# CPU.net
KiCad netlist of a schematic drawn in Altium Designer
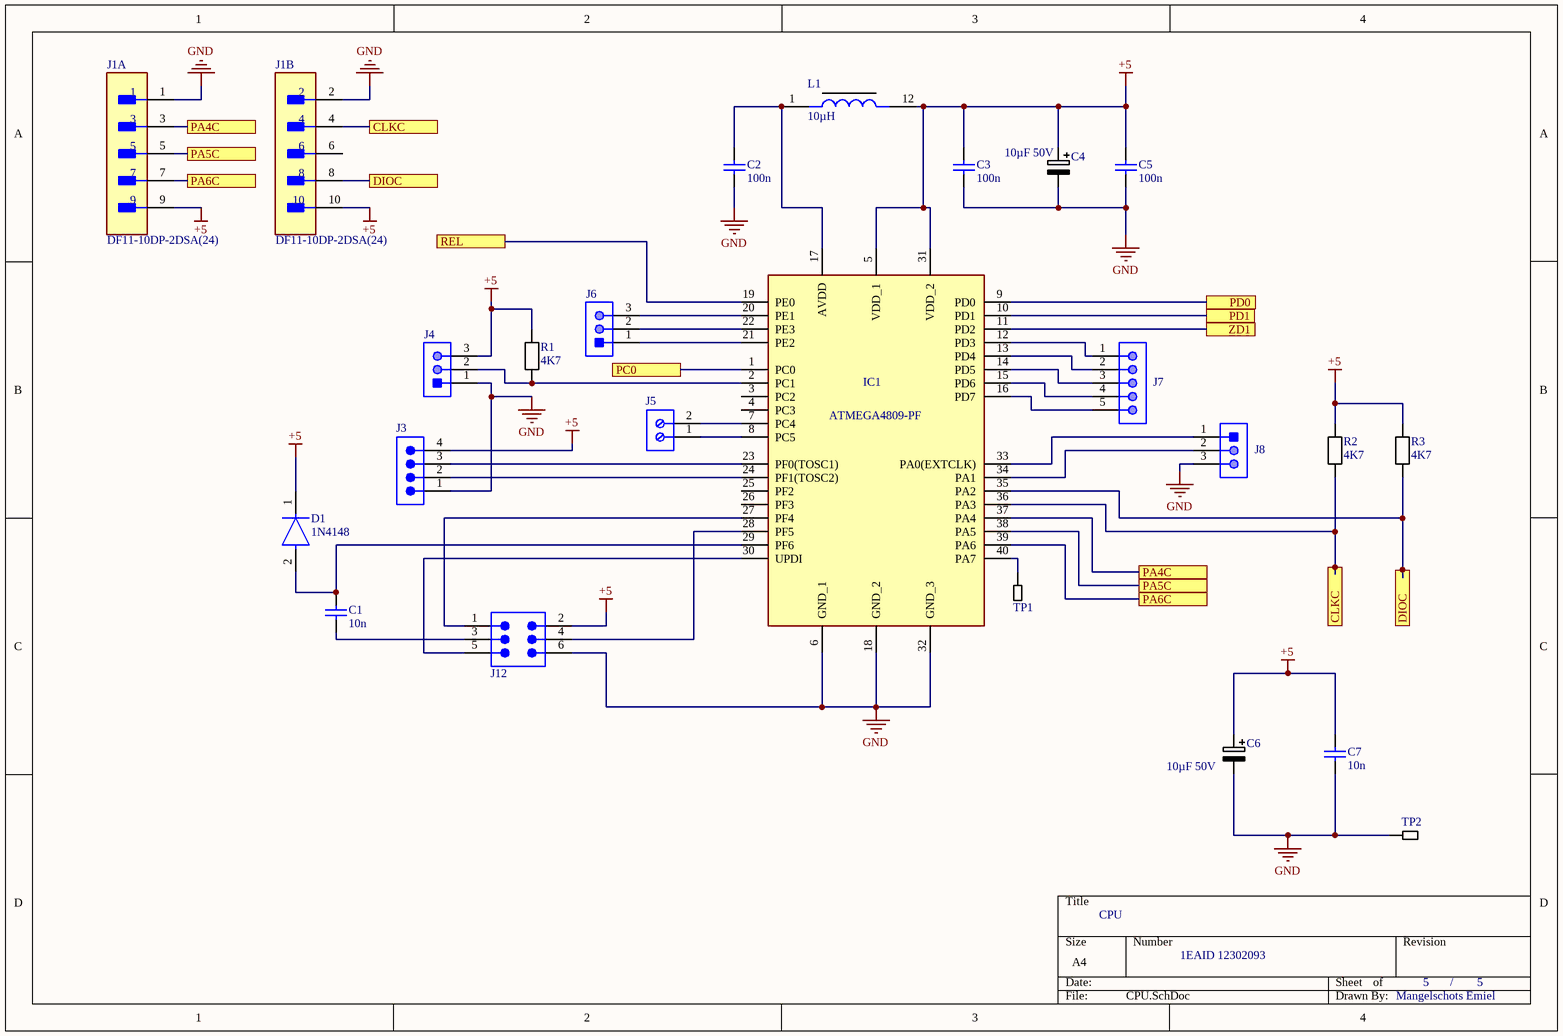
[diagram p0: CPU.SchDoc]

(export (version "E")
  (design (tool "Eeschema 10.0.6"))
  (components
    (comp (ref "C1")
      (value "10n")
      (footprint "CAPA")
      (fields (field (name "PART NUMBER") "GRM1885C1H100JA01D") (field (name "MANUFACTURER") "Murata"))
      (libsource (lib "Schlib1") (part "Capasitor"))
    )
    (comp (ref "C2")
      (value "100n")
      (footprint "CAPA")
      (fields (field (name "PART NUMBER") "GRM1885C1H100JA01D") (field (name "MANUFACTURER") "Murata"))
      (libsource (lib "Schlib1") (part "Capasitor"))
    )
    (comp (ref "C3")
      (value "100n")
      (footprint "CAPA")
      (fields (field (name "PART NUMBER") "GRM1885C1H100JA01D") (field (name "MANUFACTURER") "Murata"))
      (libsource (lib "Schlib1") (part "Capasitor"))
    )
    (comp (ref "C4")
      (value "10µF 50V")
      (footprint "CAPA1")
      (fields (field (name "PART NUMBER") "GRM1885C1H100JA01D") (field (name "MANUFACTURER") "Murata"))
      (libsource (lib "Schlib1") (part "Capasitor_1"))
    )
    (comp (ref "C5")
      (value "100n")
      (footprint "CAPA")
      (fields (field (name "PART NUMBER") "GRM1885C1H100JA01D") (field (name "MANUFACTURER") "Murata"))
      (libsource (lib "Schlib1") (part "Capasitor"))
    )
    (comp (ref "C6")
      (value "10µF 50V")
      (footprint "CAPA1")
      (fields (field (name "PART NUMBER") "GRM1885C1H100JA01D") (field (name "MANUFACTURER") "Murata"))
      (libsource (lib "Schlib1") (part "Capasitor_1"))
    )
    (comp (ref "C7")
      (value "10n")
      (footprint "CAPA")
      (fields (field (name "PART NUMBER") "GRM1885C1H100JA01D") (field (name "MANUFACTURER") "Murata"))
      (libsource (lib "Schlib1") (part "Capasitor"))
    )
    (comp (ref "D1")
      (value "1N4148")
      (footprint "DIOD")
      (description "1N4001-E3/54")
      (fields (field (name "VOLTAGE") "50V"))
      (libsource (lib "Schlib1") (part "Diode"))
    )
    (comp (ref "IC1")
      (value "ATMEGA4809-PF")
      (footprint "CPU")
      (description "IC MCU 8BIT 48KB FLASH 40DIP ATMEGA4809-PF")
      (libsource (lib "Schlib1") (part "CPU"))
    )
    (comp (ref "J1")
      (value "DF11-10DP-2DSA(24)")
      (footprint "FP-DF11-10DP-2DSA_24-MFG")
      (description "CONN HEADER VERT 10POS 2MM")
      (fields
        (field (name "OCTOPART") "https://octopart.com/df11-10dp-2dsa%2824%29-hirose-39521433")
        (field (name "MANUFACTURER") "Hirose")
      )
      (libsource (lib "Schlib1") (part "CMP-11610-000008-1"))
    )
    (comp (ref "J3")
      (value "640456-4")
      (footprint "4PinH")
      (fields (field (name "MANUFACTURER") "TE Connectivity"))
      (libsource (lib "Schlib1") (part "4Pin-Header"))
    )
    (comp (ref "J4")
      (value "B3B-PH-K-S(LF)(SN)")
      (footprint "3PinH")
      (fields (field (name "MANUFACTURER") "JST"))
      (libsource (lib "") (part "3Pin-Header_1"))
    )
    (comp (ref "J5")
      (value "1725656")
      (footprint "2 pinHeader")
      (fields (field (name "MANUFACTURER") "Phoenix Contact"))
      (libsource (lib "Schlib1") (part "2Pin-Header"))
    )
    (comp (ref "J6")
      (value "B3B-PH-K-S(LF)(SN)")
      (footprint "3PinH")
      (fields (field (name "MANUFACTURER") "JST"))
      (libsource (lib "") (part "3Pin-Header_1"))
    )
    (comp (ref "J7")
      (value "53261-0571")
      (footprint "5PinH")
      (fields (field (name "MANUFACTURER") "Molex"))
      (libsource (lib "Schlib1") (part "5Pin-Header"))
    )
    (comp (ref "J8")
      (value "B3B-PH-K-S(LF)(SN)")
      (footprint "3PinH")
      (fields (field (name "MANUFACTURER") "JST"))
      (libsource (lib "Schlib1") (part "3Pin-Header"))
    )
    (comp (ref "J12")
      (value "610106249121")
      (footprint "6Pin-Header")
      (description "CMP-1502-01146-2")
      (libsource (lib "Schlib1") (part "6Pin-Header"))
    )
    (comp (ref "L1")
      (value "10µH")
      (footprint "Smoorspoel")
      (fields (field (name "MP") "NLV25T-100J-EF") (field (name "MF") "TDK"))
      (libsource (lib "Schlib1") (part "SmoorSpoel"))
    )
    (comp (ref "R1")
      (value "4K7")
      (footprint "REST")
      (fields (field (name "MANUFACTURER") "Vishay Dale") (field (name "PART NUMBER") "CRCW08050000Z0EA"))
      (libsource (lib "Schlib1") (part "resistor"))
    )
    (comp (ref "R2")
      (value "4K7")
      (footprint "REST")
      (fields (field (name "MANUFACTURER") "Vishay Dale") (field (name "PART NUMBER") "CRCW08050000Z0EA"))
      (libsource (lib "Schlib1") (part "resistor"))
    )
    (comp (ref "R3")
      (value "4K7")
      (footprint "REST")
      (fields (field (name "MANUFACTURER") "Vishay Dale") (field (name "PART NUMBER") "CRCW08050000Z0EA"))
      (libsource (lib "Schlib1") (part "resistor"))
    )
    (comp (ref "TP1")
      (value "TP")
      (footprint "TP")
      (fields (field (name "PART NUMBER") "GRM1885C1H100JA01D") (field (name "MANUFACTURER") "Murata"))
      (libsource (lib "Schlib1") (part "TP"))
    )
    (comp (ref "TP2")
      (value "TP")
      (footprint "TP")
      (fields (field (name "PART NUMBER") "GRM1885C1H100JA01D") (field (name "MANUFACTURER") "Murata"))
      (libsource (lib "Schlib1") (part "TP"))
    )
  )
  (nets
    (net (code "1") (name "+5") (class "Default")
      (node (ref "C3") (pin "2") (pinfunction "2_2") (pintype "passive"))
      (node (ref "C4") (pin "1") (pinfunction "1_1") (pintype "passive"))
      (node (ref "C5") (pin "2") (pinfunction "2_2") (pintype "passive"))
      (node (ref "C6") (pin "1") (pinfunction "1_1") (pintype "passive"))
      (node (ref "C7") (pin "2") (pinfunction "2_2") (pintype "passive"))
      (node (ref "D1") (pin "1") (pinfunction "C_1") (pintype "passive"))
      (node (ref "IC1") (pin "31") (pinfunction "VDD_2_31") (pintype "power_in"))
      (node (ref "IC1") (pin "5") (pinfunction "VDD_1_5") (pintype "power_in"))
      (node (ref "J1") (pin "10") (pinfunction "10_10") (pintype "passive"))
      (node (ref "J1") (pin "9") (pinfunction "9_9") (pintype "passive"))
      (node (ref "J12") (pin "2") (pinfunction "2_2") (pintype "passive"))
      (node (ref "J3") (pin "4") (pinfunction "4_4") (pintype "passive"))
      (node (ref "J4") (pin "3") (pinfunction "3_3") (pintype "passive"))
      (node (ref "L1") (pin "12") (pinfunction "12_12") (pintype "passive"))
      (node (ref "R1") (pin "2") (pinfunction "2_2") (pintype "passive"))
      (node (ref "R2") (pin "2") (pinfunction "2_2") (pintype "passive"))
      (node (ref "R3") (pin "2") (pinfunction "2_2") (pintype "passive"))
    )
    (net (code "2") (name "/CLKC") (class "Default")
      (node (ref "IC1") (pin "36") (pinfunction "PA3_36") (pintype "passive"))
      (node (ref "J1") (pin "4") (pinfunction "4_4") (pintype "passive"))
      (node (ref "R2") (pin "1") (pinfunction "1_1") (pintype "passive"))
    )
    (net (code "3") (name "/DIOC") (class "Default")
      (node (ref "IC1") (pin "35") (pinfunction "PA2_35") (pintype "passive"))
      (node (ref "J1") (pin "8") (pinfunction "8_8") (pintype "passive"))
      (node (ref "R3") (pin "1") (pinfunction "1_1") (pintype "passive"))
    )
    (net (code "4") (name "/PA4C") (class "Default")
      (node (ref "IC1") (pin "37") (pinfunction "PA4_37") (pintype "passive"))
      (node (ref "J1") (pin "3") (pinfunction "3_3") (pintype "passive"))
    )
    (net (code "5") (name "/PA5C") (class "Default")
      (node (ref "IC1") (pin "38") (pinfunction "PA5_38") (pintype "passive"))
      (node (ref "J1") (pin "5") (pinfunction "5_5") (pintype "passive"))
    )
    (net (code "6") (name "/PA6C") (class "Default")
      (node (ref "IC1") (pin "39") (pinfunction "PA6_39") (pintype "passive"))
      (node (ref "J1") (pin "7") (pinfunction "7_7") (pintype "passive"))
    )
    (net (code "7") (name "/PC0") (class "Default")
      (node (ref "IC1") (pin "1") (pinfunction "PC0_1") (pintype "passive"))
    )
    (net (code "8") (name "/PD0") (class "Default")
      (node (ref "IC1") (pin "9") (pinfunction "PD0_9") (pintype "passive"))
    )
    (net (code "9") (name "/PD1") (class "Default")
      (node (ref "IC1") (pin "10") (pinfunction "PD1_10") (pintype "passive"))
    )
    (net (code "10") (name "/REL") (class "Default")
      (node (ref "IC1") (pin "19") (pinfunction "PE0_19") (pintype "passive"))
    )
    (net (code "11") (name "/ZD1") (class "Default")
      (node (ref "IC1") (pin "11") (pinfunction "PD2_11") (pintype "passive"))
    )
    (net (code "12") (name "GND") (class "Default")
      (node (ref "C2") (pin "1") (pinfunction "1_1") (pintype "passive"))
      (node (ref "C3") (pin "1") (pinfunction "1_1") (pintype "passive"))
      (node (ref "C4") (pin "2") (pinfunction "2_2") (pintype "passive"))
      (node (ref "C5") (pin "1") (pinfunction "1_1") (pintype "passive"))
      (node (ref "C6") (pin "2") (pinfunction "2_2") (pintype "passive"))
      (node (ref "C7") (pin "1") (pinfunction "1_1") (pintype "passive"))
      (node (ref "IC1") (pin "18") (pinfunction "GND_2_18") (pintype "passive"))
      (node (ref "IC1") (pin "32") (pinfunction "GND_3_32") (pintype "passive"))
      (node (ref "IC1") (pin "6") (pinfunction "GND_1_6") (pintype "passive"))
      (node (ref "J1") (pin "1") (pinfunction "1_1") (pintype "passive"))
      (node (ref "J1") (pin "2") (pinfunction "2_2") (pintype "passive"))
      (node (ref "J12") (pin "6") (pinfunction "6_6") (pintype "passive"))
      (node (ref "J3") (pin "1") (pinfunction "1_1") (pintype "passive"))
      (node (ref "J4") (pin "1") (pinfunction "1_1") (pintype "passive"))
      (node (ref "J8") (pin "3") (pinfunction "3_3") (pintype "passive"))
      (node (ref "TP2") (pin "1") (pinfunction "1_1") (pintype "passive"))
    )
    (net (code "13") (name "Net-(C1-Pad1)") (class "Default")
      (node (ref "C1") (pin "1") (pinfunction "1_1") (pintype "passive"))
      (node (ref "J12") (pin "3") (pinfunction "3_3") (pintype "passive"))
    )
    (net (code "14") (name "Net-(D1-A)") (class "Default")
      (node (ref "C1") (pin "2") (pinfunction "2_2") (pintype "passive"))
      (node (ref "D1") (pin "2") (pinfunction "A_2") (pintype "passive"))
      (node (ref "IC1") (pin "29") (pinfunction "PF6_29") (pintype "passive"))
    )
    (net (code "15") (name "Net-(IC1-AVDD)") (class "Default")
      (node (ref "C2") (pin "2") (pinfunction "2_2") (pintype "passive"))
      (node (ref "IC1") (pin "17") (pinfunction "AVDD_17") (pintype "power_in"))
      (node (ref "L1") (pin "1") (pintype "passive"))
    )
    (net (code "16") (name "Net-(IC1-PA0(EXTCLK))") (class "Default")
      (node (ref "IC1") (pin "33") (pinfunction "PA0(EXTCLK)_33") (pintype "passive"))
      (node (ref "J8") (pin "1") (pinfunction "1_1") (pintype "passive"))
    )
    (net (code "17") (name "Net-(IC1-PA1)") (class "Default")
      (node (ref "IC1") (pin "34") (pinfunction "PA1_34") (pintype "passive"))
      (node (ref "J8") (pin "2") (pinfunction "2_2") (pintype "passive"))
    )
    (net (code "18") (name "Net-(IC1-PA7)") (class "Default")
      (node (ref "IC1") (pin "40") (pinfunction "PA7_40") (pintype "passive"))
      (node (ref "TP1") (pin "1") (pinfunction "1_1") (pintype "passive"))
    )
    (net (code "19") (name "Net-(IC1-PC1)") (class "Default")
      (node (ref "IC1") (pin "2") (pinfunction "PC1_2") (pintype "passive"))
      (node (ref "J4") (pin "2") (pinfunction "2_2") (pintype "passive"))
      (node (ref "R1") (pin "1") (pinfunction "1_1") (pintype "passive"))
    )
    (net (code "20") (name "Net-(IC1-PC4)") (class "Default")
      (node (ref "IC1") (pin "7") (pinfunction "PC4_7") (pintype "passive"))
      (node (ref "J5") (pin "2") (pinfunction "2_2") (pintype "passive"))
    )
    (net (code "21") (name "Net-(IC1-PC5)") (class "Default")
      (node (ref "IC1") (pin "8") (pinfunction "PC5_8") (pintype "passive"))
      (node (ref "J5") (pin "1") (pinfunction "1_1") (pintype "passive"))
    )
    (net (code "22") (name "Net-(IC1-PD3)") (class "Default")
      (node (ref "IC1") (pin "12") (pinfunction "PD3_12") (pintype "passive"))
      (node (ref "J7") (pin "1") (pinfunction "1_1") (pintype "passive"))
    )
    (net (code "23") (name "Net-(IC1-PD4)") (class "Default")
      (node (ref "IC1") (pin "13") (pinfunction "PD4_13") (pintype "passive"))
      (node (ref "J7") (pin "2") (pinfunction "2_2") (pintype "passive"))
    )
    (net (code "24") (name "Net-(IC1-PD5)") (class "Default")
      (node (ref "IC1") (pin "14") (pinfunction "PD5_14") (pintype "passive"))
      (node (ref "J7") (pin "3") (pinfunction "3_3") (pintype "passive"))
    )
    (net (code "25") (name "Net-(IC1-PD6)") (class "Default")
      (node (ref "IC1") (pin "15") (pinfunction "PD6_15") (pintype "passive"))
      (node (ref "J7") (pin "4") (pinfunction "4_4") (pintype "passive"))
    )
    (net (code "26") (name "Net-(IC1-PD7)") (class "Default")
      (node (ref "IC1") (pin "16") (pinfunction "PD7_16") (pintype "passive"))
      (node (ref "J7") (pin "5") (pinfunction "5_5") (pintype "passive"))
    )
    (net (code "27") (name "Net-(IC1-PE1)") (class "Default")
      (node (ref "IC1") (pin "20") (pinfunction "PE1_20") (pintype "passive"))
      (node (ref "J6") (pin "3") (pinfunction "3_3") (pintype "passive"))
    )
    (net (code "28") (name "Net-(IC1-PE2)") (class "Default")
      (node (ref "IC1") (pin "21") (pinfunction "PE2_21") (pintype "passive"))
      (node (ref "J6") (pin "1") (pinfunction "1_1") (pintype "passive"))
    )
    (net (code "29") (name "Net-(IC1-PE3)") (class "Default")
      (node (ref "IC1") (pin "22") (pinfunction "PE3_22") (pintype "passive"))
      (node (ref "J6") (pin "2") (pinfunction "2_2") (pintype "passive"))
    )
    (net (code "30") (name "Net-(IC1-PF0(TOSC1))") (class "Default")
      (node (ref "IC1") (pin "23") (pinfunction "PF0(TOSC1)_23") (pintype "passive"))
      (node (ref "J3") (pin "3") (pinfunction "3_3") (pintype "passive"))
    )
    (net (code "31") (name "Net-(IC1-PF1(TOSC2))") (class "Default")
      (node (ref "IC1") (pin "24") (pinfunction "PF1(TOSC2)_24") (pintype "passive"))
      (node (ref "J3") (pin "2") (pinfunction "2_2") (pintype "passive"))
    )
    (net (code "32") (name "Net-(IC1-PF4)") (class "Default")
      (node (ref "IC1") (pin "27") (pinfunction "PF4_27") (pintype "passive"))
      (node (ref "J12") (pin "1") (pinfunction "1_1") (pintype "passive"))
    )
    (net (code "33") (name "Net-(IC1-PF5)") (class "Default")
      (node (ref "IC1") (pin "28") (pinfunction "PF5_28") (pintype "passive"))
      (node (ref "J12") (pin "4") (pinfunction "4_4") (pintype "passive"))
    )
    (net (code "34") (name "Net-(IC1-UPDI)") (class "Default")
      (node (ref "IC1") (pin "30") (pinfunction "UPDI_30") (pintype "passive"))
      (node (ref "J12") (pin "5") (pinfunction "5_5") (pintype "passive"))
    )
    (net (code "35") (name "unconnected-(IC1-PC2-Pad3)") (class "Default")
      (node (ref "IC1") (pin "3") (pinfunction "PC2_3") (pintype "passive"))
    )
    (net (code "36") (name "unconnected-(IC1-PC3-Pad4)") (class "Default")
      (node (ref "IC1") (pin "4") (pinfunction "PC3_4") (pintype "passive"))
    )
    (net (code "37") (name "unconnected-(IC1-PF2-Pad25)") (class "Default")
      (node (ref "IC1") (pin "25") (pinfunction "PF2_25") (pintype "passive"))
    )
    (net (code "38") (name "unconnected-(IC1-PF3-Pad26)") (class "Default")
      (node (ref "IC1") (pin "26") (pinfunction "PF3_26") (pintype "passive"))
    )
    (net (code "39") (name "unconnected-(J1-Pad6)") (class "Default")
      (node (ref "J1") (pin "6") (pinfunction "6_6") (pintype "passive"))
    )
  )
)
